# LED_ring_V2.net
KiCad netlist of a schematic drawn in Altium Designer
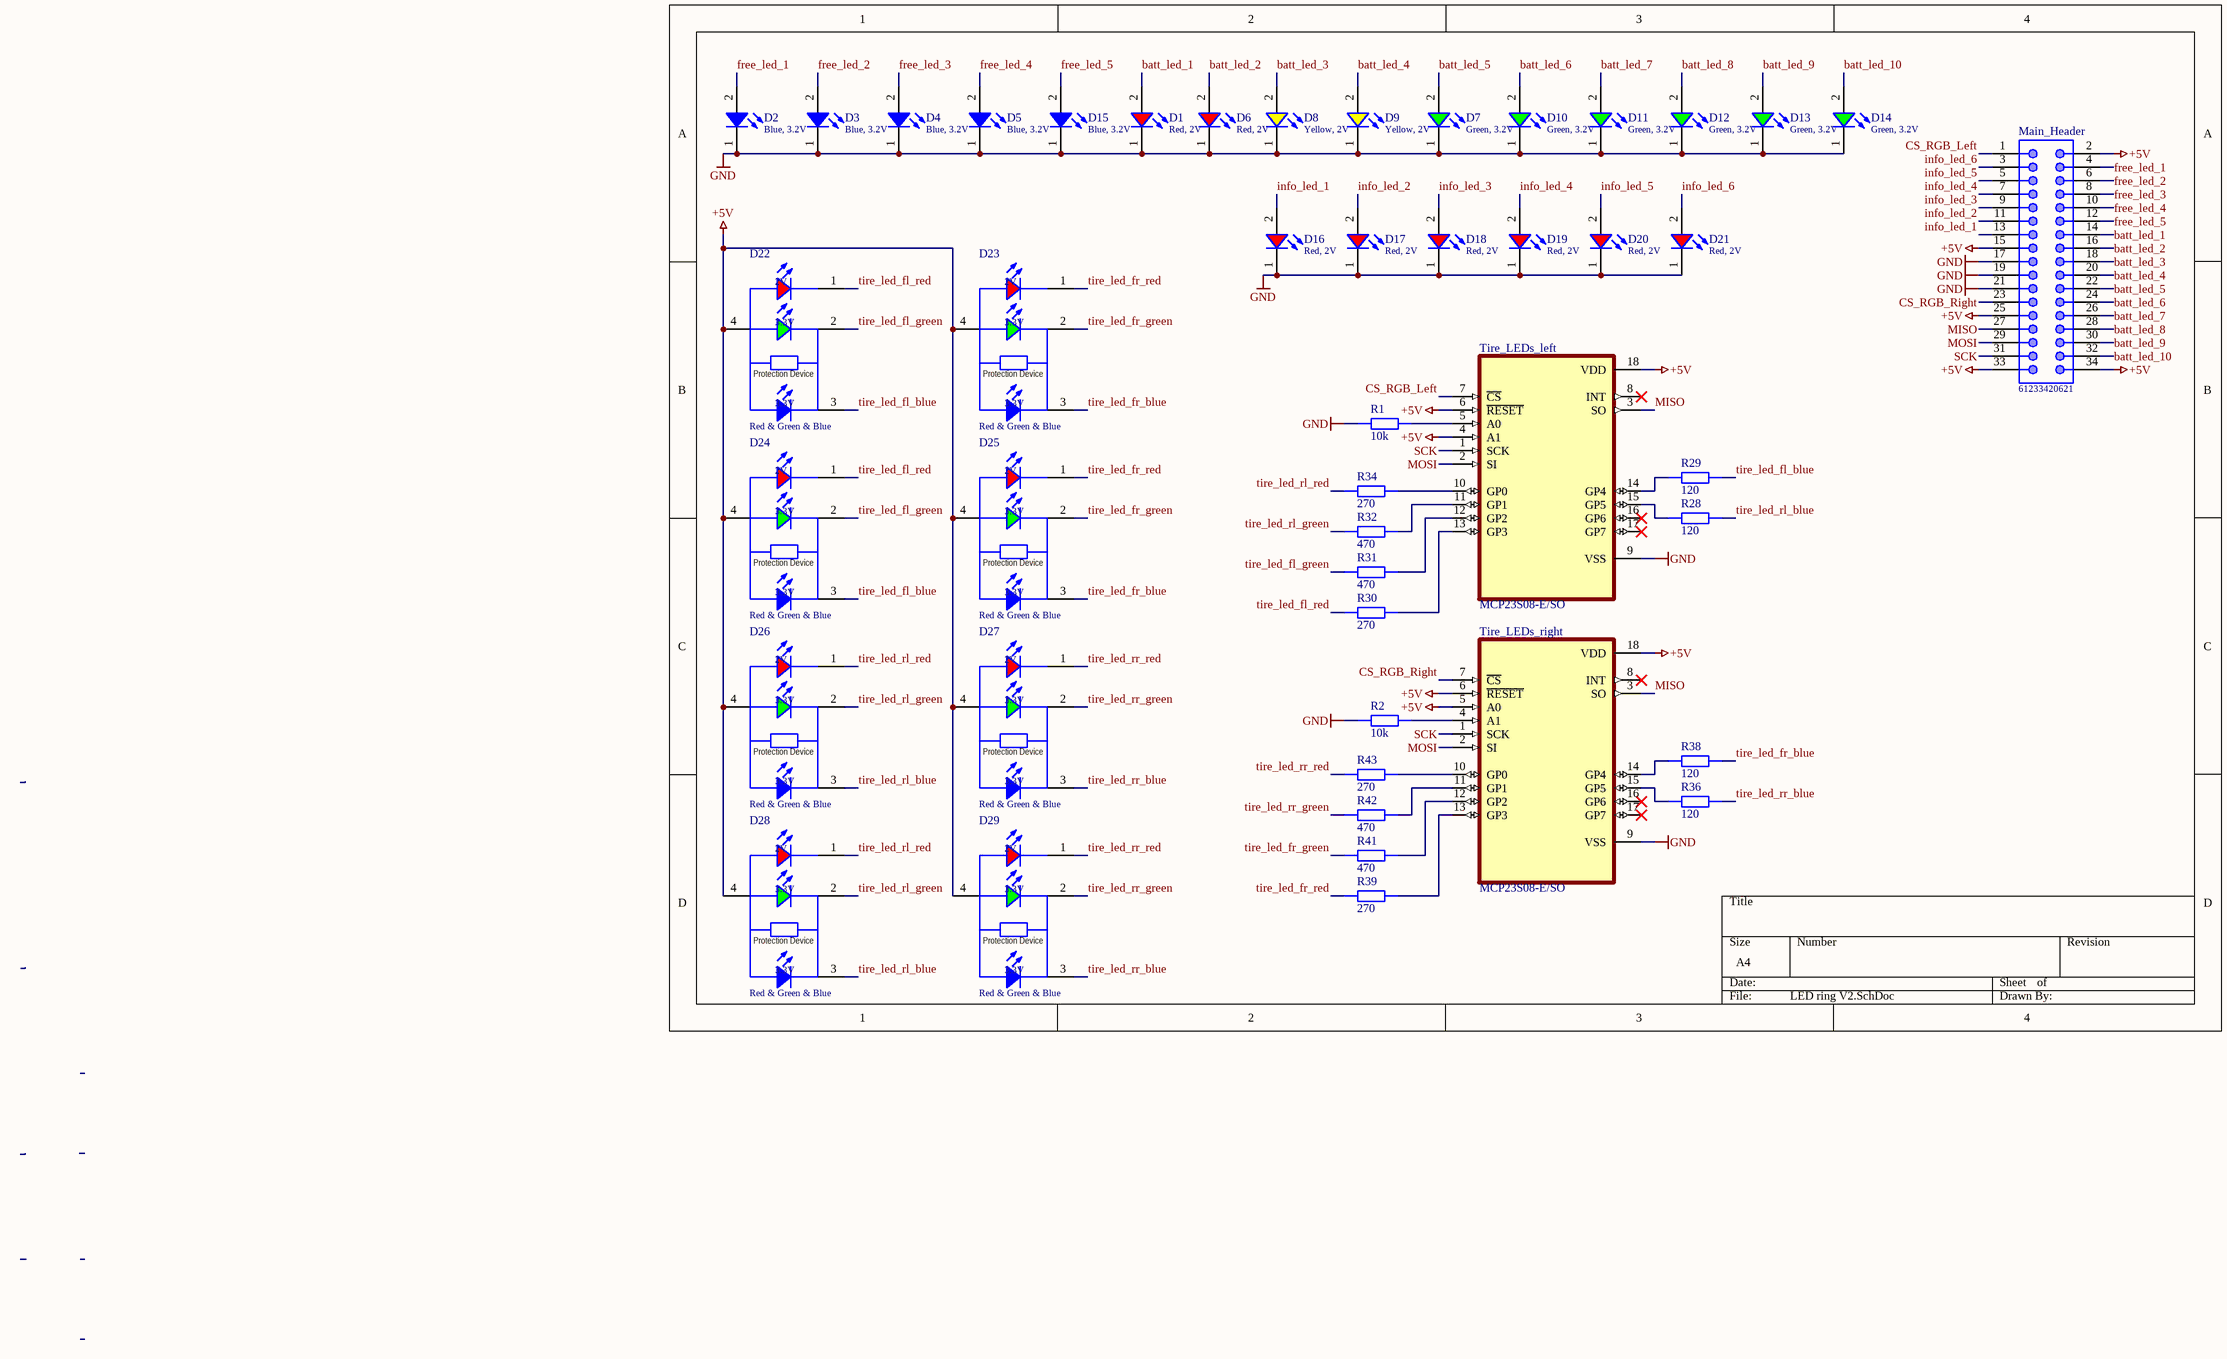
[diagram p0: LED ring V2.SchDoc]

(export (version "E")
  (design (tool "Eeschema 10.0.6"))
  (components
    (comp (ref "D1")
      (value "Red, 2V")
      (footprint "WL-SMCW_0805")
      (description "WL-SMCW SMT Mono-color Chip LED Waterclear, size 0805, Red, 2V, 140deg")
      (fields (field (name "PART NUMBER") "150080RS75000") (field (name "PUBLISHER") "Wurth Elektronik"))
      (libsource (lib "Altium_WL-SMCW (rev20a)") (part "150080RS75000"))
    )
    (comp (ref "D2")
      (value "Blue, 3.2V")
      (footprint "WL-SMCW_0805")
      (description "WL-SMCW SMT Mono-color Chip LED Waterclear, size 0805, Blue, 3.2V, 140deg")
      (fields (field (name "PART NUMBER") "150080BS75000") (field (name "PUBLISHER") "Wurth Elektronik"))
      (libsource (lib "Altium_WL-SMCW (rev20a)") (part "150080BS75000"))
    )
    (comp (ref "D3")
      (value "Blue, 3.2V")
      (footprint "WL-SMCW_0805")
      (description "WL-SMCW SMT Mono-color Chip LED Waterclear, size 0805, Blue, 3.2V, 140deg")
      (fields (field (name "PART NUMBER") "150080BS75000") (field (name "PUBLISHER") "Wurth Elektronik"))
      (libsource (lib "Altium_WL-SMCW (rev20a)") (part "150080BS75000"))
    )
    (comp (ref "D4")
      (value "Blue, 3.2V")
      (footprint "WL-SMCW_0805")
      (description "WL-SMCW SMT Mono-color Chip LED Waterclear, size 0805, Blue, 3.2V, 140deg")
      (fields (field (name "PART NUMBER") "150080BS75000") (field (name "PUBLISHER") "Wurth Elektronik"))
      (libsource (lib "Altium_WL-SMCW (rev20a)") (part "150080BS75000"))
    )
    (comp (ref "D5")
      (value "Blue, 3.2V")
      (footprint "WL-SMCW_0805")
      (description "WL-SMCW SMT Mono-color Chip LED Waterclear, size 0805, Blue, 3.2V, 140deg")
      (fields (field (name "PART NUMBER") "150080BS75000") (field (name "PUBLISHER") "Wurth Elektronik"))
      (libsource (lib "Altium_WL-SMCW (rev20a)") (part "150080BS75000"))
    )
    (comp (ref "D6")
      (value "Red, 2V")
      (footprint "WL-SMCW_0805")
      (description "WL-SMCW SMT Mono-color Chip LED Waterclear, size 0805, Red, 2V, 140deg")
      (fields (field (name "PART NUMBER") "150080RS75000") (field (name "PUBLISHER") "Wurth Elektronik"))
      (libsource (lib "Altium_WL-SMCW (rev20a)") (part "150080RS75000"))
    )
    (comp (ref "D7")
      (value "Green, 3.2V")
      (footprint "WL-SMCW_0805")
      (description "WL-SMCW SMT Mono-color Chip LED Waterclear, size 0805, Green, 3.2V, 140deg")
      (fields (field (name "PART NUMBER") "150080GS75000") (field (name "PUBLISHER") "Wurth Elektronik"))
      (libsource (lib "Altium_WL-SMCW (rev20a)") (part "150080GS75000"))
    )
    (comp (ref "D8")
      (value "Yellow, 2V")
      (footprint "WL-SMCW_0805")
      (description "WL-SMCW SMT Mono-color Chip LED Waterclear, size 0805, Yellow, 2V, 140deg")
      (fields (field (name "PART NUMBER") "150080YS75000") (field (name "PUBLISHER") "Wurth Elektronik"))
      (libsource (lib "Altium_WL-SMCW (rev20a)") (part "150080YS75000"))
    )
    (comp (ref "D9")
      (value "Yellow, 2V")
      (footprint "WL-SMCW_0805")
      (description "WL-SMCW SMT Mono-color Chip LED Waterclear, size 0805, Yellow, 2V, 140deg")
      (fields (field (name "PART NUMBER") "150080YS75000") (field (name "PUBLISHER") "Wurth Elektronik"))
      (libsource (lib "Altium_WL-SMCW (rev20a)") (part "150080YS75000"))
    )
    (comp (ref "D10")
      (value "Green, 3.2V")
      (footprint "WL-SMCW_0805")
      (description "WL-SMCW SMT Mono-color Chip LED Waterclear, size 0805, Green, 3.2V, 140deg")
      (fields (field (name "PART NUMBER") "150080GS75000") (field (name "PUBLISHER") "Wurth Elektronik"))
      (libsource (lib "Altium_WL-SMCW (rev20a)") (part "150080GS75000"))
    )
    (comp (ref "D11")
      (value "Green, 3.2V")
      (footprint "WL-SMCW_0805")
      (description "WL-SMCW SMT Mono-color Chip LED Waterclear, size 0805, Green, 3.2V, 140deg")
      (fields (field (name "PART NUMBER") "150080GS75000") (field (name "PUBLISHER") "Wurth Elektronik"))
      (libsource (lib "Altium_WL-SMCW (rev20a)") (part "150080GS75000"))
    )
    (comp (ref "D12")
      (value "Green, 3.2V")
      (footprint "WL-SMCW_0805")
      (description "WL-SMCW SMT Mono-color Chip LED Waterclear, size 0805, Green, 3.2V, 140deg")
      (fields (field (name "PART NUMBER") "150080GS75000") (field (name "PUBLISHER") "Wurth Elektronik"))
      (libsource (lib "Altium_WL-SMCW (rev20a)") (part "150080GS75000"))
    )
    (comp (ref "D13")
      (value "Green, 3.2V")
      (footprint "WL-SMCW_0805")
      (description "WL-SMCW SMT Mono-color Chip LED Waterclear, size 0805, Green, 3.2V, 140deg")
      (fields (field (name "PART NUMBER") "150080GS75000") (field (name "PUBLISHER") "Wurth Elektronik"))
      (libsource (lib "Altium_WL-SMCW (rev20a)") (part "150080GS75000"))
    )
    (comp (ref "D14")
      (value "Green, 3.2V")
      (footprint "WL-SMCW_0805")
      (description "WL-SMCW SMT Mono-color Chip LED Waterclear, size 0805, Green, 3.2V, 140deg")
      (fields (field (name "PART NUMBER") "150080GS75000") (field (name "PUBLISHER") "Wurth Elektronik"))
      (libsource (lib "Altium_WL-SMCW (rev20a)") (part "150080GS75000"))
    )
    (comp (ref "D15")
      (value "Blue, 3.2V")
      (footprint "WL-SMCW_0805")
      (description "WL-SMCW SMT Mono-color Chip LED Waterclear, size 0805, Blue, 3.2V, 140deg")
      (fields (field (name "PART NUMBER") "150080BS75000") (field (name "PUBLISHER") "Wurth Elektronik"))
      (libsource (lib "Altium_WL-SMCW (rev20a)") (part "150080BS75000"))
    )
    (comp (ref "D16")
      (value "Red, 2V")
      (footprint "WL-SMCW_0805")
      (description "WL-SMCW SMT Mono-color Chip LED Waterclear, size 0805, Red, 2V, 140deg")
      (fields (field (name "PART NUMBER") "150080RS75000") (field (name "PUBLISHER") "Wurth Elektronik"))
      (libsource (lib "Altium_WL-SMCW (rev20a)") (part "150080RS75000"))
    )
    (comp (ref "D17")
      (value "Red, 2V")
      (footprint "WL-SMCW_0805")
      (description "WL-SMCW SMT Mono-color Chip LED Waterclear, size 0805, Red, 2V, 140deg")
      (fields (field (name "PART NUMBER") "150080RS75000") (field (name "PUBLISHER") "Wurth Elektronik"))
      (libsource (lib "Altium_WL-SMCW (rev20a)") (part "150080RS75000"))
    )
    (comp (ref "D18")
      (value "Red, 2V")
      (footprint "WL-SMCW_0805")
      (description "WL-SMCW SMT Mono-color Chip LED Waterclear, size 0805, Red, 2V, 140deg")
      (fields (field (name "PART NUMBER") "150080RS75000") (field (name "PUBLISHER") "Wurth Elektronik"))
      (libsource (lib "Altium_WL-SMCW (rev20a)") (part "150080RS75000"))
    )
    (comp (ref "D19")
      (value "Red, 2V")
      (footprint "WL-SMCW_0805")
      (description "WL-SMCW SMT Mono-color Chip LED Waterclear, size 0805, Red, 2V, 140deg")
      (fields (field (name "PART NUMBER") "150080RS75000") (field (name "PUBLISHER") "Wurth Elektronik"))
      (libsource (lib "Altium_WL-SMCW (rev20a)") (part "150080RS75000"))
    )
    (comp (ref "D20")
      (value "Red, 2V")
      (footprint "WL-SMCW_0805")
      (description "WL-SMCW SMT Mono-color Chip LED Waterclear, size 0805, Red, 2V, 140deg")
      (fields (field (name "PART NUMBER") "150080RS75000") (field (name "PUBLISHER") "Wurth Elektronik"))
      (libsource (lib "Altium_WL-SMCW (rev20a)") (part "150080RS75000"))
    )
    (comp (ref "D21")
      (value "Red, 2V")
      (footprint "WL-SMCW_0805")
      (description "WL-SMCW SMT Mono-color Chip LED Waterclear, size 0805, Red, 2V, 140deg")
      (fields (field (name "PART NUMBER") "150080RS75000") (field (name "PUBLISHER") "Wurth Elektronik"))
      (libsource (lib "Altium_WL-SMCW (rev20a)") (part "150080RS75000"))
    )
    (comp (ref "D22")
      (value "Red & Green & Blue")
      (footprint "WL-SFCW_0805")
      (description "WL-SFCW SMT Full-color Chip LED Waterclear, size 0805, Red & Green & Blue, 120deg")
      (fields (field (name "PART NUMBER") "150080M173000") (field (name "PUBLISHER") "Wurth Elektronik"))
      (libsource (lib "Altium_WL-SFCW (rev19b)") (part "150080M173000"))
    )
    (comp (ref "D23")
      (value "Red & Green & Blue")
      (footprint "WL-SFCW_0805")
      (description "WL-SFCW SMT Full-color Chip LED Waterclear, size 0805, Red & Green & Blue, 120deg")
      (fields (field (name "PART NUMBER") "150080M173000") (field (name "PUBLISHER") "Wurth Elektronik"))
      (libsource (lib "Altium_WL-SFCW (rev19b)") (part "150080M173000"))
    )
    (comp (ref "D24")
      (value "Red & Green & Blue")
      (footprint "WL-SFCW_0805")
      (description "WL-SFCW SMT Full-color Chip LED Waterclear, size 0805, Red & Green & Blue, 120deg")
      (fields (field (name "PART NUMBER") "150080M173000") (field (name "PUBLISHER") "Wurth Elektronik"))
      (libsource (lib "Altium_WL-SFCW (rev19b)") (part "150080M173000"))
    )
    (comp (ref "D25")
      (value "Red & Green & Blue")
      (footprint "WL-SFCW_0805")
      (description "WL-SFCW SMT Full-color Chip LED Waterclear, size 0805, Red & Green & Blue, 120deg")
      (fields (field (name "PART NUMBER") "150080M173000") (field (name "PUBLISHER") "Wurth Elektronik"))
      (libsource (lib "Altium_WL-SFCW (rev19b)") (part "150080M173000"))
    )
    (comp (ref "D26")
      (value "Red & Green & Blue")
      (footprint "WL-SFCW_0805")
      (description "WL-SFCW SMT Full-color Chip LED Waterclear, size 0805, Red & Green & Blue, 120deg")
      (fields (field (name "PART NUMBER") "150080M173000") (field (name "PUBLISHER") "Wurth Elektronik"))
      (libsource (lib "Altium_WL-SFCW (rev19b)") (part "150080M173000"))
    )
    (comp (ref "D27")
      (value "Red & Green & Blue")
      (footprint "WL-SFCW_0805")
      (description "WL-SFCW SMT Full-color Chip LED Waterclear, size 0805, Red & Green & Blue, 120deg")
      (fields (field (name "PART NUMBER") "150080M173000") (field (name "PUBLISHER") "Wurth Elektronik"))
      (libsource (lib "Altium_WL-SFCW (rev19b)") (part "150080M173000"))
    )
    (comp (ref "D28")
      (value "Red & Green & Blue")
      (footprint "WL-SFCW_0805")
      (description "WL-SFCW SMT Full-color Chip LED Waterclear, size 0805, Red & Green & Blue, 120deg")
      (fields (field (name "PART NUMBER") "150080M173000") (field (name "PUBLISHER") "Wurth Elektronik"))
      (libsource (lib "Altium_WL-SFCW (rev19b)") (part "150080M173000"))
    )
    (comp (ref "D29")
      (value "Red & Green & Blue")
      (footprint "WL-SFCW_0805")
      (description "WL-SFCW SMT Full-color Chip LED Waterclear, size 0805, Red & Green & Blue, 120deg")
      (fields (field (name "PART NUMBER") "150080M173000") (field (name "PUBLISHER") "Wurth Elektronik"))
      (libsource (lib "Altium_WL-SFCW (rev19b)") (part "150080M173000"))
    )
    (comp (ref "Main_Header")
      (value "61233420621")
      (footprint "61233420621")
      (description "WR-BHD Box Header, Male PCB side, pitch 2.54mm, SMT, Straight, 34p")
      (fields (field (name "MANUFACTURER") "Wurth Elektronik"))
      (libsource (lib "Altium_WR-BHD (rev21a)") (part "61233420621"))
    )
    (comp (ref "R1")
      (value "10k")
      (footprint "STACKPOLE CSR0603")
      (description "Resistor with multiple footprints")
      (fields (field (name "Comment") "SMD Resistor"))
      (libsource (lib "Standardbauteile") (part "SMD Resistor"))
    )
    (comp (ref "R2")
      (value "10k")
      (footprint "STACKPOLE CSR0603")
      (description "Resistor with multiple footprints")
      (fields (field (name "Comment") "SMD Resistor"))
      (libsource (lib "Standardbauteile") (part "SMD Resistor"))
    )
    (comp (ref "R28")
      (value "120")
      (footprint "STACKPOLE CSR0603")
      (description "Resistor with multiple footprints")
      (fields (field (name "Comment") "SMD Resistor"))
      (libsource (lib "Standardbauteile") (part "SMD Resistor"))
    )
    (comp (ref "R29")
      (value "120")
      (footprint "STACKPOLE CSR0603")
      (description "Resistor with multiple footprints")
      (fields (field (name "Comment") "SMD Resistor"))
      (libsource (lib "Standardbauteile") (part "SMD Resistor"))
    )
    (comp (ref "R30")
      (value "270")
      (footprint "STACKPOLE CSR0603")
      (description "Resistor with multiple footprints")
      (fields (field (name "Comment") "SMD Resistor"))
      (libsource (lib "Standardbauteile") (part "SMD Resistor"))
    )
    (comp (ref "R31")
      (value "470")
      (footprint "STACKPOLE CSR0603")
      (description "Resistor with multiple footprints")
      (fields (field (name "Comment") "SMD Resistor"))
      (libsource (lib "Standardbauteile") (part "SMD Resistor"))
    )
    (comp (ref "R32")
      (value "470")
      (footprint "STACKPOLE CSR0603")
      (description "Resistor with multiple footprints")
      (fields (field (name "Comment") "SMD Resistor"))
      (libsource (lib "Standardbauteile") (part "SMD Resistor"))
    )
    (comp (ref "R34")
      (value "270")
      (footprint "STACKPOLE CSR0603")
      (description "Resistor with multiple footprints")
      (fields (field (name "Comment") "SMD Resistor"))
      (libsource (lib "Standardbauteile") (part "SMD Resistor"))
    )
    (comp (ref "R36")
      (value "120")
      (footprint "STACKPOLE CSR0603")
      (description "Resistor with multiple footprints")
      (fields (field (name "Comment") "SMD Resistor"))
      (libsource (lib "Standardbauteile") (part "SMD Resistor"))
    )
    (comp (ref "R38")
      (value "120")
      (footprint "STACKPOLE CSR0603")
      (description "Resistor with multiple footprints")
      (fields (field (name "Comment") "SMD Resistor"))
      (libsource (lib "Standardbauteile") (part "SMD Resistor"))
    )
    (comp (ref "R39")
      (value "270")
      (footprint "STACKPOLE CSR0603")
      (description "Resistor with multiple footprints")
      (fields (field (name "Comment") "SMD Resistor"))
      (libsource (lib "Standardbauteile") (part "SMD Resistor"))
    )
    (comp (ref "R41")
      (value "470")
      (footprint "STACKPOLE CSR0603")
      (description "Resistor with multiple footprints")
      (fields (field (name "Comment") "SMD Resistor"))
      (libsource (lib "Standardbauteile") (part "SMD Resistor"))
    )
    (comp (ref "R42")
      (value "470")
      (footprint "STACKPOLE CSR0603")
      (description "Resistor with multiple footprints")
      (fields (field (name "Comment") "SMD Resistor"))
      (libsource (lib "Standardbauteile") (part "SMD Resistor"))
    )
    (comp (ref "R43")
      (value "270")
      (footprint "STACKPOLE CSR0603")
      (description "Resistor with multiple footprints")
      (fields (field (name "Comment") "SMD Resistor"))
      (libsource (lib "Standardbauteile") (part "SMD Resistor"))
    )
    (comp (ref "Tire_LEDs_left")
      (value "MCP23S08-E/SO")
      (footprint "SOIC127P1030X265-18N")
      (description "I/O Expander 8 SPI 10MHz 18-SOIC")
      (fields (field (name "MF") "Microchip"))
      (libsource (lib "MCP23S08-E_SO") (part "MCP23S08-E/SO"))
    )
    (comp (ref "Tire_LEDs_right")
      (value "MCP23S08-E/SO")
      (footprint "SOIC127P1030X265-18N")
      (description "I/O Expander 8 SPI 10MHz 18-SOIC")
      (fields (field (name "MF") "Microchip"))
      (libsource (lib "MCP23S08-E_SO") (part "MCP23S08-E/SO"))
    )
  )
  (nets
    (net (code "1") (name "+5V") (class "Default")
      (node (ref "D22") (pin "4") (pinfunction "A_4") (pintype "passive"))
      (node (ref "D23") (pin "4") (pinfunction "A_4") (pintype "passive"))
      (node (ref "D24") (pin "4") (pinfunction "A_4") (pintype "passive"))
      (node (ref "D25") (pin "4") (pinfunction "A_4") (pintype "passive"))
      (node (ref "D26") (pin "4") (pinfunction "A_4") (pintype "passive"))
      (node (ref "D27") (pin "4") (pinfunction "A_4") (pintype "passive"))
      (node (ref "D28") (pin "4") (pinfunction "A_4") (pintype "passive"))
      (node (ref "D29") (pin "4") (pinfunction "A_4") (pintype "passive"))
      (node (ref "Main_Header") (pin "15") (pinfunction "15_15") (pintype "passive"))
      (node (ref "Main_Header") (pin "2") (pinfunction "2_2") (pintype "passive"))
      (node (ref "Main_Header") (pin "25") (pinfunction "25_25") (pintype "passive"))
      (node (ref "Main_Header") (pin "33") (pinfunction "33_33") (pintype "passive"))
      (node (ref "Main_Header") (pin "34") (pinfunction "34_34") (pintype "passive"))
      (node (ref "Tire_LEDs_left") (pin "18") (pinfunction "VDD_18") (pintype "power_in"))
      (node (ref "Tire_LEDs_left") (pin "4") (pinfunction "A1_4") (pintype "input"))
      (node (ref "Tire_LEDs_left") (pin "6") (pinfunction "~{RESET}_6") (pintype "input"))
      (node (ref "Tire_LEDs_right") (pin "18") (pinfunction "VDD_18") (pintype "power_in"))
      (node (ref "Tire_LEDs_right") (pin "5") (pinfunction "A0_5") (pintype "input"))
      (node (ref "Tire_LEDs_right") (pin "6") (pinfunction "~{RESET}_6") (pintype "input"))
    )
    (net (code "2") (name "/CS_RGB_Left") (class "Default")
      (node (ref "Main_Header") (pin "1") (pinfunction "1_1") (pintype "passive"))
      (node (ref "Tire_LEDs_left") (pin "7") (pinfunction "~{CS}_7") (pintype "input"))
    )
    (net (code "3") (name "/CS_RGB_Right") (class "Default")
      (node (ref "Main_Header") (pin "23") (pinfunction "23_23") (pintype "passive"))
      (node (ref "Tire_LEDs_right") (pin "7") (pinfunction "~{CS}_7") (pintype "input"))
    )
    (net (code "4") (name "/MISO") (class "Default")
      (node (ref "Main_Header") (pin "27") (pinfunction "27_27") (pintype "passive"))
      (node (ref "Tire_LEDs_left") (pin "3") (pinfunction "SO_3") (pintype "output"))
      (node (ref "Tire_LEDs_right") (pin "3") (pinfunction "SO_3") (pintype "output"))
    )
    (net (code "5") (name "/MOSI") (class "Default")
      (node (ref "Main_Header") (pin "29") (pinfunction "29_29") (pintype "passive"))
      (node (ref "Tire_LEDs_left") (pin "2") (pinfunction "SI_2") (pintype "input"))
      (node (ref "Tire_LEDs_right") (pin "2") (pinfunction "SI_2") (pintype "input"))
    )
    (net (code "6") (name "/SCK") (class "Default")
      (node (ref "Main_Header") (pin "31") (pinfunction "31_31") (pintype "passive"))
      (node (ref "Tire_LEDs_left") (pin "1") (pinfunction "SCK_1") (pintype "input"))
      (node (ref "Tire_LEDs_right") (pin "1") (pinfunction "SCK_1") (pintype "input"))
    )
    (net (code "7") (name "/batt_led_1") (class "Default")
      (node (ref "D1") (pin "2") (pinfunction "A_2") (pintype "passive"))
      (node (ref "Main_Header") (pin "14") (pinfunction "14_14") (pintype "passive"))
    )
    (net (code "8") (name "/batt_led_2") (class "Default")
      (node (ref "D6") (pin "2") (pinfunction "A_2") (pintype "passive"))
      (node (ref "Main_Header") (pin "16") (pinfunction "16_16") (pintype "passive"))
    )
    (net (code "9") (name "/batt_led_3") (class "Default")
      (node (ref "D8") (pin "2") (pinfunction "A_2") (pintype "passive"))
      (node (ref "Main_Header") (pin "18") (pinfunction "18_18") (pintype "passive"))
    )
    (net (code "10") (name "/batt_led_4") (class "Default")
      (node (ref "D9") (pin "2") (pinfunction "A_2") (pintype "passive"))
      (node (ref "Main_Header") (pin "20") (pinfunction "20_20") (pintype "passive"))
    )
    (net (code "11") (name "/batt_led_5") (class "Default")
      (node (ref "D7") (pin "2") (pinfunction "A_2") (pintype "passive"))
      (node (ref "Main_Header") (pin "22") (pinfunction "22_22") (pintype "passive"))
    )
    (net (code "12") (name "/batt_led_6") (class "Default")
      (node (ref "D10") (pin "2") (pinfunction "A_2") (pintype "passive"))
      (node (ref "Main_Header") (pin "24") (pinfunction "24_24") (pintype "passive"))
    )
    (net (code "13") (name "/batt_led_7") (class "Default")
      (node (ref "D11") (pin "2") (pinfunction "A_2") (pintype "passive"))
      (node (ref "Main_Header") (pin "26") (pinfunction "26_26") (pintype "passive"))
    )
    (net (code "14") (name "/batt_led_8") (class "Default")
      (node (ref "D12") (pin "2") (pinfunction "A_2") (pintype "passive"))
      (node (ref "Main_Header") (pin "28") (pinfunction "28_28") (pintype "passive"))
    )
    (net (code "15") (name "/batt_led_9") (class "Default")
      (node (ref "D13") (pin "2") (pinfunction "A_2") (pintype "passive"))
      (node (ref "Main_Header") (pin "30") (pinfunction "30_30") (pintype "passive"))
    )
    (net (code "16") (name "/batt_led_10") (class "Default")
      (node (ref "D14") (pin "2") (pinfunction "A_2") (pintype "passive"))
      (node (ref "Main_Header") (pin "32") (pinfunction "32_32") (pintype "passive"))
    )
    (net (code "17") (name "/free_led_1") (class "Default")
      (node (ref "D2") (pin "2") (pinfunction "A_2") (pintype "passive"))
      (node (ref "Main_Header") (pin "4") (pinfunction "4_4") (pintype "passive"))
    )
    (net (code "18") (name "/free_led_2") (class "Default")
      (node (ref "D3") (pin "2") (pinfunction "A_2") (pintype "passive"))
      (node (ref "Main_Header") (pin "6") (pinfunction "6_6") (pintype "passive"))
    )
    (net (code "19") (name "/free_led_3") (class "Default")
      (node (ref "D4") (pin "2") (pinfunction "A_2") (pintype "passive"))
      (node (ref "Main_Header") (pin "8") (pinfunction "8_8") (pintype "passive"))
    )
    (net (code "20") (name "/free_led_4") (class "Default")
      (node (ref "D5") (pin "2") (pinfunction "A_2") (pintype "passive"))
      (node (ref "Main_Header") (pin "10") (pinfunction "10_10") (pintype "passive"))
    )
    (net (code "21") (name "/free_led_5") (class "Default")
      (node (ref "D15") (pin "2") (pinfunction "A_2") (pintype "passive"))
      (node (ref "Main_Header") (pin "12") (pinfunction "12_12") (pintype "passive"))
    )
    (net (code "22") (name "/info_led_1") (class "Default")
      (node (ref "D16") (pin "2") (pinfunction "A_2") (pintype "passive"))
      (node (ref "Main_Header") (pin "13") (pinfunction "13_13") (pintype "passive"))
    )
    (net (code "23") (name "/info_led_2") (class "Default")
      (node (ref "D17") (pin "2") (pinfunction "A_2") (pintype "passive"))
      (node (ref "Main_Header") (pin "11") (pinfunction "11_11") (pintype "passive"))
    )
    (net (code "24") (name "/info_led_3") (class "Default")
      (node (ref "D18") (pin "2") (pinfunction "A_2") (pintype "passive"))
      (node (ref "Main_Header") (pin "9") (pinfunction "9_9") (pintype "passive"))
    )
    (net (code "25") (name "/info_led_4") (class "Default")
      (node (ref "D19") (pin "2") (pinfunction "A_2") (pintype "passive"))
      (node (ref "Main_Header") (pin "7") (pinfunction "7_7") (pintype "passive"))
    )
    (net (code "26") (name "/info_led_5") (class "Default")
      (node (ref "D20") (pin "2") (pinfunction "A_2") (pintype "passive"))
      (node (ref "Main_Header") (pin "5") (pinfunction "5_5") (pintype "passive"))
    )
    (net (code "27") (name "/info_led_6") (class "Default")
      (node (ref "D21") (pin "2") (pinfunction "A_2") (pintype "passive"))
      (node (ref "Main_Header") (pin "3") (pinfunction "3_3") (pintype "passive"))
    )
    (net (code "28") (name "/tire_led_fl_blue") (class "Default")
      (node (ref "D22") (pin "3") (pinfunction "K_3") (pintype "passive"))
      (node (ref "D24") (pin "3") (pinfunction "K_3") (pintype "passive"))
      (node (ref "R29") (pin "2") (pinfunction "2_2") (pintype "passive"))
    )
    (net (code "29") (name "/tire_led_fl_green") (class "Default")
      (node (ref "D22") (pin "2") (pinfunction "K_2") (pintype "passive"))
      (node (ref "D24") (pin "2") (pinfunction "K_2") (pintype "passive"))
      (node (ref "R31") (pin "2") (pinfunction "2_2") (pintype "passive"))
    )
    (net (code "30") (name "/tire_led_fl_red") (class "Default")
      (node (ref "D22") (pin "1") (pinfunction "K_1") (pintype "passive"))
      (node (ref "D24") (pin "1") (pinfunction "K_1") (pintype "passive"))
      (node (ref "R30") (pin "2") (pinfunction "2_2") (pintype "passive"))
    )
    (net (code "31") (name "/tire_led_fr_blue") (class "Default")
      (node (ref "D23") (pin "3") (pinfunction "K_3") (pintype "passive"))
      (node (ref "D25") (pin "3") (pinfunction "K_3") (pintype "passive"))
      (node (ref "R38") (pin "2") (pinfunction "2_2") (pintype "passive"))
    )
    (net (code "32") (name "/tire_led_fr_green") (class "Default")
      (node (ref "D23") (pin "2") (pinfunction "K_2") (pintype "passive"))
      (node (ref "D25") (pin "2") (pinfunction "K_2") (pintype "passive"))
      (node (ref "R41") (pin "2") (pinfunction "2_2") (pintype "passive"))
    )
    (net (code "33") (name "/tire_led_fr_red") (class "Default")
      (node (ref "D23") (pin "1") (pinfunction "K_1") (pintype "passive"))
      (node (ref "D25") (pin "1") (pinfunction "K_1") (pintype "passive"))
      (node (ref "R39") (pin "2") (pinfunction "2_2") (pintype "passive"))
    )
    (net (code "34") (name "/tire_led_rl_blue") (class "Default")
      (node (ref "D26") (pin "3") (pinfunction "K_3") (pintype "passive"))
      (node (ref "D28") (pin "3") (pinfunction "K_3") (pintype "passive"))
      (node (ref "R28") (pin "2") (pinfunction "2_2") (pintype "passive"))
    )
    (net (code "35") (name "/tire_led_rl_green") (class "Default")
      (node (ref "D26") (pin "2") (pinfunction "K_2") (pintype "passive"))
      (node (ref "D28") (pin "2") (pinfunction "K_2") (pintype "passive"))
      (node (ref "R32") (pin "2") (pinfunction "2_2") (pintype "passive"))
    )
    (net (code "36") (name "/tire_led_rl_red") (class "Default")
      (node (ref "D26") (pin "1") (pinfunction "K_1") (pintype "passive"))
      (node (ref "D28") (pin "1") (pinfunction "K_1") (pintype "passive"))
      (node (ref "R34") (pin "2") (pinfunction "2_2") (pintype "passive"))
    )
    (net (code "37") (name "/tire_led_rr_blue") (class "Default")
      (node (ref "D27") (pin "3") (pinfunction "K_3") (pintype "passive"))
      (node (ref "D29") (pin "3") (pinfunction "K_3") (pintype "passive"))
      (node (ref "R36") (pin "2") (pinfunction "2_2") (pintype "passive"))
    )
    (net (code "38") (name "/tire_led_rr_green") (class "Default")
      (node (ref "D27") (pin "2") (pinfunction "K_2") (pintype "passive"))
      (node (ref "D29") (pin "2") (pinfunction "K_2") (pintype "passive"))
      (node (ref "R42") (pin "2") (pinfunction "2_2") (pintype "passive"))
    )
    (net (code "39") (name "/tire_led_rr_red") (class "Default")
      (node (ref "D27") (pin "1") (pinfunction "K_1") (pintype "passive"))
      (node (ref "D29") (pin "1") (pinfunction "K_1") (pintype "passive"))
      (node (ref "R43") (pin "2") (pinfunction "2_2") (pintype "passive"))
    )
    (net (code "40") (name "GND") (class "Default")
      (node (ref "D1") (pin "1") (pinfunction "K_1") (pintype "passive"))
      (node (ref "D10") (pin "1") (pinfunction "K_1") (pintype "passive"))
      (node (ref "D11") (pin "1") (pinfunction "K_1") (pintype "passive"))
      (node (ref "D12") (pin "1") (pinfunction "K_1") (pintype "passive"))
      (node (ref "D13") (pin "1") (pinfunction "K_1") (pintype "passive"))
      (node (ref "D14") (pin "1") (pinfunction "K_1") (pintype "passive"))
      (node (ref "D15") (pin "1") (pinfunction "K_1") (pintype "passive"))
      (node (ref "D16") (pin "1") (pinfunction "K_1") (pintype "passive"))
      (node (ref "D17") (pin "1") (pinfunction "K_1") (pintype "passive"))
      (node (ref "D18") (pin "1") (pinfunction "K_1") (pintype "passive"))
      (node (ref "D19") (pin "1") (pinfunction "K_1") (pintype "passive"))
      (node (ref "D2") (pin "1") (pinfunction "K_1") (pintype "passive"))
      (node (ref "D20") (pin "1") (pinfunction "K_1") (pintype "passive"))
      (node (ref "D21") (pin "1") (pinfunction "K_1") (pintype "passive"))
      (node (ref "D3") (pin "1") (pinfunction "K_1") (pintype "passive"))
      (node (ref "D4") (pin "1") (pinfunction "K_1") (pintype "passive"))
      (node (ref "D5") (pin "1") (pinfunction "K_1") (pintype "passive"))
      (node (ref "D6") (pin "1") (pinfunction "K_1") (pintype "passive"))
      (node (ref "D7") (pin "1") (pinfunction "K_1") (pintype "passive"))
      (node (ref "D8") (pin "1") (pinfunction "K_1") (pintype "passive"))
      (node (ref "D9") (pin "1") (pinfunction "K_1") (pintype "passive"))
      (node (ref "Main_Header") (pin "17") (pinfunction "17_17") (pintype "passive"))
      (node (ref "Main_Header") (pin "19") (pinfunction "19_19") (pintype "passive"))
      (node (ref "Main_Header") (pin "21") (pinfunction "21_21") (pintype "passive"))
      (node (ref "R1") (pin "2") (pinfunction "2_2") (pintype "passive"))
      (node (ref "R2") (pin "2") (pinfunction "2_2") (pintype "passive"))
      (node (ref "Tire_LEDs_left") (pin "9") (pinfunction "VSS_9") (pintype "power_in"))
      (node (ref "Tire_LEDs_right") (pin "9") (pinfunction "VSS_9") (pintype "power_in"))
    )
    (net (code "41") (name "Net-(Tire_LEDs_left-A0)") (class "Default")
      (node (ref "R1") (pin "1") (pinfunction "1_1") (pintype "passive"))
      (node (ref "Tire_LEDs_left") (pin "5") (pinfunction "A0_5") (pintype "input"))
    )
    (net (code "42") (name "Net-(Tire_LEDs_left-GP0)") (class "Default")
      (node (ref "R34") (pin "1") (pinfunction "1_1") (pintype "passive"))
      (node (ref "Tire_LEDs_left") (pin "10") (pinfunction "GP0_10") (pintype "bidirectional"))
    )
    (net (code "43") (name "Net-(Tire_LEDs_left-GP1)") (class "Default")
      (node (ref "R32") (pin "1") (pinfunction "1_1") (pintype "passive"))
      (node (ref "Tire_LEDs_left") (pin "11") (pinfunction "GP1_11") (pintype "bidirectional"))
    )
    (net (code "44") (name "Net-(Tire_LEDs_left-GP2)") (class "Default")
      (node (ref "R31") (pin "1") (pinfunction "1_1") (pintype "passive"))
      (node (ref "Tire_LEDs_left") (pin "12") (pinfunction "GP2_12") (pintype "bidirectional"))
    )
    (net (code "45") (name "Net-(Tire_LEDs_left-GP3)") (class "Default")
      (node (ref "R30") (pin "1") (pinfunction "1_1") (pintype "passive"))
      (node (ref "Tire_LEDs_left") (pin "13") (pinfunction "GP3_13") (pintype "bidirectional"))
    )
    (net (code "46") (name "Net-(Tire_LEDs_left-GP4)") (class "Default")
      (node (ref "R29") (pin "1") (pinfunction "1_1") (pintype "passive"))
      (node (ref "Tire_LEDs_left") (pin "14") (pinfunction "GP4_14") (pintype "bidirectional"))
    )
    (net (code "47") (name "Net-(Tire_LEDs_left-GP5)") (class "Default")
      (node (ref "R28") (pin "1") (pinfunction "1_1") (pintype "passive"))
      (node (ref "Tire_LEDs_left") (pin "15") (pinfunction "GP5_15") (pintype "bidirectional"))
    )
    (net (code "48") (name "Net-(Tire_LEDs_right-A1)") (class "Default")
      (node (ref "R2") (pin "1") (pinfunction "1_1") (pintype "passive"))
      (node (ref "Tire_LEDs_right") (pin "4") (pinfunction "A1_4") (pintype "input"))
    )
    (net (code "49") (name "Net-(Tire_LEDs_right-GP0)") (class "Default")
      (node (ref "R43") (pin "1") (pinfunction "1_1") (pintype "passive"))
      (node (ref "Tire_LEDs_right") (pin "10") (pinfunction "GP0_10") (pintype "bidirectional"))
    )
    (net (code "50") (name "Net-(Tire_LEDs_right-GP1)") (class "Default")
      (node (ref "R42") (pin "1") (pinfunction "1_1") (pintype "passive"))
      (node (ref "Tire_LEDs_right") (pin "11") (pinfunction "GP1_11") (pintype "bidirectional"))
    )
    (net (code "51") (name "Net-(Tire_LEDs_right-GP2)") (class "Default")
      (node (ref "R41") (pin "1") (pinfunction "1_1") (pintype "passive"))
      (node (ref "Tire_LEDs_right") (pin "12") (pinfunction "GP2_12") (pintype "bidirectional"))
    )
    (net (code "52") (name "Net-(Tire_LEDs_right-GP3)") (class "Default")
      (node (ref "R39") (pin "1") (pinfunction "1_1") (pintype "passive"))
      (node (ref "Tire_LEDs_right") (pin "13") (pinfunction "GP3_13") (pintype "bidirectional"))
    )
    (net (code "53") (name "Net-(Tire_LEDs_right-GP4)") (class "Default")
      (node (ref "R38") (pin "1") (pinfunction "1_1") (pintype "passive"))
      (node (ref "Tire_LEDs_right") (pin "14") (pinfunction "GP4_14") (pintype "bidirectional"))
    )
    (net (code "54") (name "Net-(Tire_LEDs_right-GP5)") (class "Default")
      (node (ref "R36") (pin "1") (pinfunction "1_1") (pintype "passive"))
      (node (ref "Tire_LEDs_right") (pin "15") (pinfunction "GP5_15") (pintype "bidirectional"))
    )
    (net (code "55") (name "unconnected-(Tire_LEDs_left-GP6-Pad16)") (class "Default")
      (node (ref "Tire_LEDs_left") (pin "16") (pinfunction "GP6_16") (pintype "bidirectional+no_connect"))
    )
    (net (code "56") (name "unconnected-(Tire_LEDs_left-GP7-Pad17)") (class "Default")
      (node (ref "Tire_LEDs_left") (pin "17") (pinfunction "GP7_17") (pintype "bidirectional+no_connect"))
    )
    (net (code "57") (name "unconnected-(Tire_LEDs_left-INT-Pad8)") (class "Default")
      (node (ref "Tire_LEDs_left") (pin "8") (pinfunction "INT_8") (pintype "output+no_connect"))
    )
    (net (code "58") (name "unconnected-(Tire_LEDs_right-GP6-Pad16)") (class "Default")
      (node (ref "Tire_LEDs_right") (pin "16") (pinfunction "GP6_16") (pintype "bidirectional+no_connect"))
    )
    (net (code "59") (name "unconnected-(Tire_LEDs_right-GP7-Pad17)") (class "Default")
      (node (ref "Tire_LEDs_right") (pin "17") (pinfunction "GP7_17") (pintype "bidirectional+no_connect"))
    )
    (net (code "60") (name "unconnected-(Tire_LEDs_right-INT-Pad8)") (class "Default")
      (node (ref "Tire_LEDs_right") (pin "8") (pinfunction "INT_8") (pintype "output+no_connect"))
    )
  )
)
